# InterfaceBoard.net
KiCad netlist of a schematic drawn in Altium Designer
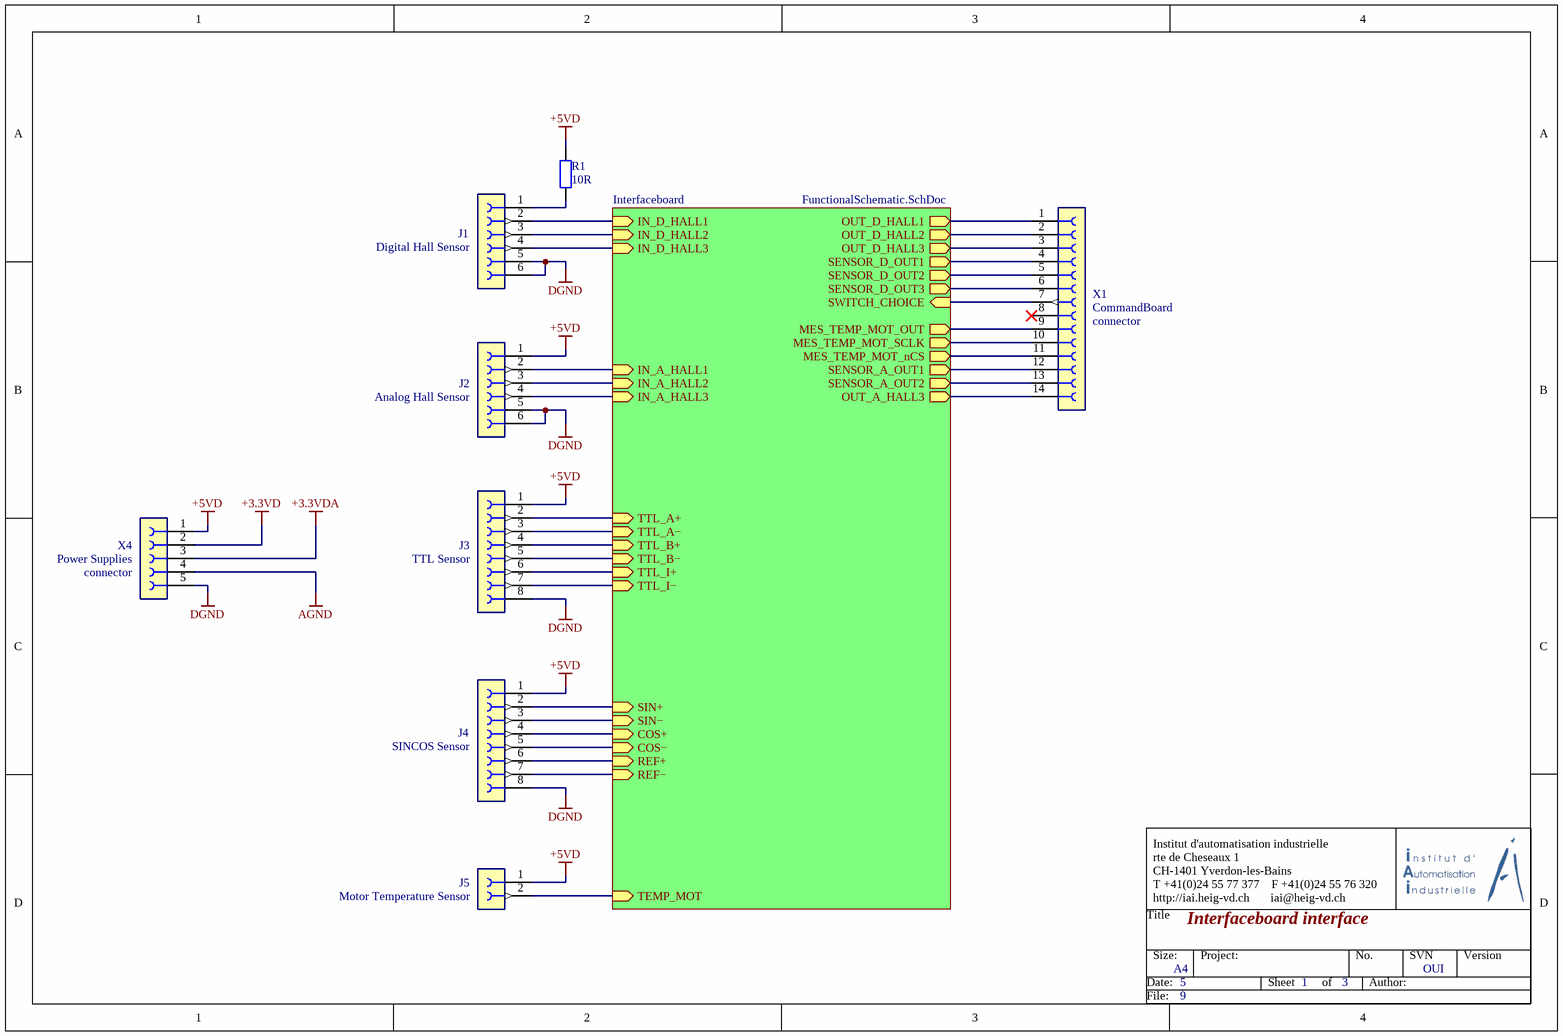
[diagram p0: InterfaceBoard.SchDoc]

(export (version "E")
  (design (tool "Eeschema 10.0.6"))
  (components
    (comp (ref "J1")
      (value "CONNECT SMD 6pos 180°")
      (footprint "InterfaceBoard:TE_7-215079-6")
      (fields (field (name "USE") "Digital Hall Sensor"))
      (libsource (lib "InterfaceBoard") (part "CONNECT SMD 6pos 180° 2.54mm"))
    )
    (comp (ref "J2")
      (value "CONNECT SMD 6pos 180°")
      (footprint "InterfaceBoard:TE_7-215079-6")
      (fields (field (name "USE") "Analog Hall Sensor"))
      (libsource (lib "InterfaceBoard") (part "CONNECT SMD 6pos 180° 2.54mm"))
    )
    (comp (ref "J3")
      (value "CONNECT SMD 8pos 180°")
      (footprint "InterfaceBoard:TE_7-215079-8")
      (fields (field (name "USE") "TTL Sensor"))
      (libsource (lib "InterfaceBoard") (part "CONNECT SMD 8pos 180° 2.54mm"))
    )
    (comp (ref "J4")
      (value "CONNECT SMD 8pos 180°")
      (footprint "InterfaceBoard:TE_7-215079-8")
      (fields (field (name "USE") "SINCOS Sensor"))
      (libsource (lib "InterfaceBoard") (part "CONNECT SMD 8pos 180° 2.54mm"))
    )
    (comp (ref "J5")
      (value "CONNECT 2pos 90°")
      (footprint "InterfaceBoard:62000611821 - 2pin")
      (fields (field (name "USE") "Motor Temperature Sensor"))
      (libsource (lib "InterfaceBoard") (part "CONNECT 2pos 90° 3.81mm"))
    )
    (comp (ref "R1")
      (value "10R")
      (footprint "InterfaceBoard:RESC1508X04N")
      (description "10 Ohms ±1% 0,1W, 1/10W Pavé résistif 0603 (1608 métrique) AutomobileAEC-Q200 Couche épaisse")
      (fields (field (name "Comment") "RES SMD 10R 0603"))
      (libsource (lib "InterfaceBoard") (part "RES SMD 10 OHM 1% 1/10W 0603"))
    )
    (comp (ref "X1")
      (value "CONNECT SMD 16pos 180°")
      (footprint "InterfaceBoard:62301421021")
      (fields (field (name "USE") "CommandBoard") (field (name "SYSTEM") "connector"))
      (libsource (lib "InterfaceBoard") (part "CONNECT SMD 14pos 180° 2.54mm"))
    )
    (comp (ref "X4")
      (value "CONNECT HEADER 5pos 180°")
      (footprint "InterfaceBoard:62000611821 - 5pin")
      (fields (field (name "USE") "Power Supplies") (field (name "SYSTEM") "connector"))
      (libsource (lib "InterfaceBoard") (part "CONNECT HEADER 5pos 180° 2mm"))
    )
  )
  (nets
    (net (code "1") (name "+3.3VD") (class "Default")
      (node (ref "X4") (pin "2") (pinfunction "2_2") (pintype "passive"))
    )
    (net (code "2") (name "+3.3VDA") (class "Default")
      (node (ref "X4") (pin "3") (pinfunction "3_3") (pintype "passive"))
    )
    (net (code "3") (name "+5VD") (class "Default")
      (node (ref "J2") (pin "1") (pinfunction "1_1") (pintype "passive"))
      (node (ref "J3") (pin "1") (pinfunction "1_1") (pintype "passive"))
      (node (ref "J4") (pin "1") (pinfunction "1_1") (pintype "passive"))
      (node (ref "J5") (pin "1") (pinfunction "1_1") (pintype "passive"))
      (node (ref "R1") (pin "2") (pinfunction "2_2") (pintype "passive"))
      (node (ref "X4") (pin "1") (pinfunction "1_1") (pintype "passive"))
    )
    (net (code "4") (name "/COS+") (class "Default")
      (node (ref "J4") (pin "4") (pinfunction "4_4") (pintype "output"))
    )
    (net (code "5") (name "/COS−") (class "Default")
      (node (ref "J4") (pin "5") (pinfunction "5_5") (pintype "output"))
    )
    (net (code "6") (name "/IN_A_HALL1") (class "Default")
      (node (ref "J2") (pin "2") (pinfunction "2_2") (pintype "output"))
    )
    (net (code "7") (name "/IN_A_HALL2") (class "Default")
      (node (ref "J2") (pin "3") (pinfunction "3_3") (pintype "output"))
    )
    (net (code "8") (name "/IN_A_HALL3") (class "Default")
      (node (ref "J2") (pin "4") (pinfunction "4_4") (pintype "output"))
    )
    (net (code "9") (name "/IN_D_HALL1") (class "Default")
      (node (ref "J1") (pin "2") (pinfunction "2_2") (pintype "output"))
    )
    (net (code "10") (name "/IN_D_HALL2") (class "Default")
      (node (ref "J1") (pin "3") (pinfunction "3_3") (pintype "output"))
    )
    (net (code "11") (name "/IN_D_HALL3") (class "Default")
      (node (ref "J1") (pin "4") (pinfunction "4_4") (pintype "output"))
    )
    (net (code "12") (name "/MES_TEMP_MOT_OUT") (class "Default")
      (node (ref "X1") (pin "9") (pinfunction "9_9") (pintype "passive"))
    )
    (net (code "13") (name "/MES_TEMP_MOT_SCLK") (class "Default")
      (node (ref "X1") (pin "10") (pinfunction "10_10") (pintype "passive"))
    )
    (net (code "14") (name "/MES_TEMP_MOT_nCS") (class "Default")
      (node (ref "X1") (pin "11") (pinfunction "11_11") (pintype "passive"))
    )
    (net (code "15") (name "/OUT_A_HALL3") (class "Default")
      (node (ref "X1") (pin "14") (pinfunction "14_14") (pintype "passive"))
    )
    (net (code "16") (name "/OUT_D_HALL1") (class "Default")
      (node (ref "X1") (pin "1") (pinfunction "1_1") (pintype "passive"))
    )
    (net (code "17") (name "/OUT_D_HALL2") (class "Default")
      (node (ref "X1") (pin "2") (pinfunction "2_2") (pintype "passive"))
    )
    (net (code "18") (name "/OUT_D_HALL3") (class "Default")
      (node (ref "X1") (pin "3") (pinfunction "3_3") (pintype "passive"))
    )
    (net (code "19") (name "/REF+") (class "Default")
      (node (ref "J4") (pin "6") (pinfunction "6_6") (pintype "output"))
    )
    (net (code "20") (name "/REF−") (class "Default")
      (node (ref "J4") (pin "7") (pinfunction "7_7") (pintype "output"))
    )
    (net (code "21") (name "/SENSOR_A_OUT1") (class "Default")
      (node (ref "X1") (pin "12") (pinfunction "12_12") (pintype "passive"))
    )
    (net (code "22") (name "/SENSOR_A_OUT2") (class "Default")
      (node (ref "X1") (pin "13") (pinfunction "13_13") (pintype "passive"))
    )
    (net (code "23") (name "/SENSOR_D_OUT1") (class "Default")
      (node (ref "X1") (pin "4") (pinfunction "4_4") (pintype "passive"))
    )
    (net (code "24") (name "/SENSOR_D_OUT2") (class "Default")
      (node (ref "X1") (pin "5") (pinfunction "5_5") (pintype "passive"))
    )
    (net (code "25") (name "/SENSOR_D_OUT3") (class "Default")
      (node (ref "X1") (pin "6") (pinfunction "6_6") (pintype "passive"))
    )
    (net (code "26") (name "/SIN+") (class "Default")
      (node (ref "J4") (pin "2") (pinfunction "2_2") (pintype "output"))
    )
    (net (code "27") (name "/SIN−") (class "Default")
      (node (ref "J4") (pin "3") (pinfunction "3_3") (pintype "output"))
    )
    (net (code "28") (name "/SWITCH_CHOICE") (class "Default")
      (node (ref "X1") (pin "7") (pinfunction "7_7") (pintype "output"))
    )
    (net (code "29") (name "/TEMP_MOT") (class "Default")
      (node (ref "J5") (pin "2") (pinfunction "2_2") (pintype "output"))
    )
    (net (code "30") (name "/TTL_A+") (class "Default")
      (node (ref "J3") (pin "2") (pinfunction "2_2") (pintype "output"))
    )
    (net (code "31") (name "/TTL_A−") (class "Default")
      (node (ref "J3") (pin "3") (pinfunction "3_3") (pintype "output"))
    )
    (net (code "32") (name "/TTL_B+") (class "Default")
      (node (ref "J3") (pin "4") (pinfunction "4_4") (pintype "output"))
    )
    (net (code "33") (name "/TTL_B−") (class "Default")
      (node (ref "J3") (pin "5") (pinfunction "5_5") (pintype "output"))
    )
    (net (code "34") (name "/TTL_I+") (class "Default")
      (node (ref "J3") (pin "6") (pinfunction "6_6") (pintype "output"))
    )
    (net (code "35") (name "/TTL_I−") (class "Default")
      (node (ref "J3") (pin "7") (pinfunction "7_7") (pintype "output"))
    )
    (net (code "36") (name "AGND") (class "Default")
      (node (ref "X4") (pin "4") (pinfunction "4_4") (pintype "passive"))
    )
    (net (code "37") (name "DGND") (class "Default")
      (node (ref "J1") (pin "5") (pinfunction "5_5") (pintype "passive"))
      (node (ref "J1") (pin "6") (pinfunction "6_6") (pintype "passive"))
      (node (ref "J2") (pin "5") (pinfunction "5_5") (pintype "passive"))
      (node (ref "J2") (pin "6") (pinfunction "6_6") (pintype "passive"))
      (node (ref "J3") (pin "8") (pinfunction "8_8") (pintype "passive"))
      (node (ref "J4") (pin "8") (pinfunction "8_8") (pintype "passive"))
      (node (ref "X4") (pin "5") (pinfunction "5_5") (pintype "passive"))
    )
    (net (code "38") (name "Net-(J1-Pad1)") (class "Default")
      (node (ref "J1") (pin "1") (pinfunction "1_1") (pintype "passive"))
      (node (ref "R1") (pin "1") (pinfunction "1_1") (pintype "passive"))
    )
    (net (code "39") (name "unconnected-(X1-Pad8)") (class "Default")
      (node (ref "X1") (pin "8") (pinfunction "8_8") (pintype "passive+no_connect"))
    )
  )
)
